# pca20017_power.net
KiCad netlist of a schematic drawn in Altium Designer
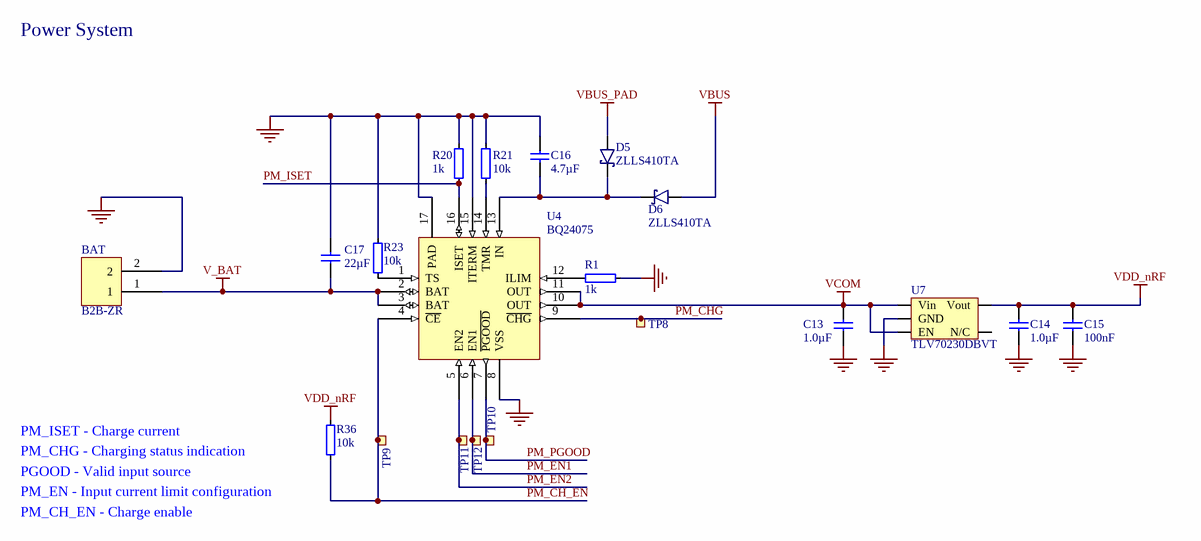
[diagram p0: pca20017_power.SchDoc]

(export (version "E")
  (design (tool "Eeschema 10.0.6"))
  (components
    (comp (ref "BAT")
      (value "B2B-ZR")
      (footprint "B2B-ZR")
      (description "CONN JST 2POS 0.059\" (1.50mm)")
      (fields
        (field (name "MANUFACTURER") "JST Sales America Inc")
        (field (name "MANUFACTURER PART NUMBER") "B2B-ZR(LF)(SN)")
        (field (name "PUBLISHER") "Nordic Semiconductor")
      )
      (libsource (lib "Nordic Passive DB") (part "B2B-ZR"))
    )
    (comp (ref "C13")
      (value "1.0µF")
      (footprint "CAPC1005X04L")
      (description "Capacitor, X5R, ±5%")
      (fields (field (name "PART NUMBER") "C0402-1µ0") (field (name "PUBLISHER") "Nordic Semiconductor"))
      (libsource (lib "Nordic Passive DB") (part "CAP"))
    )
    (comp (ref "C14")
      (value "1.0µF")
      (footprint "CAPC1005X04L")
      (description "Capacitor, X5R, ±5%")
      (fields (field (name "PART NUMBER") "C0402-1µ0") (field (name "PUBLISHER") "Nordic Semiconductor"))
      (libsource (lib "Nordic Passive DB") (part "CAP"))
    )
    (comp (ref "C15")
      (value "100nF")
      (footprint "CAPC1005X04L")
      (description "Capacitor, X7R, ±10%")
      (fields (field (name "PART NUMBER") "C0402-100n") (field (name "PUBLISHER") "Nordic Semiconductor"))
      (libsource (lib "Nordic Passive DB") (part "CAP"))
    )
    (comp (ref "C16")
      (value "4.7µF")
      (footprint "CAPC1005X04L")
      (description "Capacitor, X5R, ±20%")
      (fields (field (name "PART NUMBER") "C0402-4µ7") (field (name "PUBLISHER") "Nordic Semiconductor"))
      (libsource (lib "Nordic Passive DB") (part "CAP"))
    )
    (comp (ref "C17")
      (value "22µF")
      (footprint "CAPC2012X11L")
      (description "Capacitor, X5R, ±10%")
      (fields (field (name "PART NUMBER") "C0805-22µ") (field (name "PUBLISHER") "Nordic Semiconductor"))
      (libsource (lib "Nordic Passive DB") (part "CAP"))
    )
    (comp (ref "D5")
      (value "ZLLS410TA")
      (footprint "SOD-323")
      (description "DIODE SCHOTTKY 10V 0.57A SOD323")
      (fields
        (field (name "MANUFACTURER") "Diodes Incorporated")
        (field (name "2ND SOURCE PART NUMBER") "522-ZLLS410TA")
        (field (name "PUBLISHER") "Nordic Semiconductor")
      )
      (libsource (lib "Nordic Discrete DB") (part "D{colon}SCHOTTKY"))
    )
    (comp (ref "D6")
      (value "ZLLS410TA")
      (footprint "SOD-323")
      (description "DIODE SCHOTTKY 10V 0.57A SOD323")
      (fields
        (field (name "MANUFACTURER") "Diodes Incorporated")
        (field (name "2ND SOURCE PART NUMBER") "522-ZLLS410TA")
        (field (name "PUBLISHER") "Nordic Semiconductor")
      )
      (libsource (lib "Nordic Discrete DB") (part "D{colon}SCHOTTKY"))
    )
    (comp (ref "R1")
      (value "1k")
      (footprint "RESC1005X04L")
      (description "Resistor, ±1%, 0.063W")
      (fields (field (name "PART NUMBER") "R0402-1k0") (field (name "PUBLISHER") "Nordic Semiconductor"))
      (libsource (lib "Nordic Passive DB") (part "RES_1"))
    )
    (comp (ref "R20")
      (value "1k")
      (footprint "RESC1005X04L")
      (description "Resistor, ±1%, 0.063W")
      (fields (field (name "PART NUMBER") "R0402-1k0") (field (name "PUBLISHER") "Nordic Semiconductor"))
      (libsource (lib "Nordic Passive DB") (part "RES_1"))
    )
    (comp (ref "R21")
      (value "10k")
      (footprint "RESC1005X04L")
      (description "Resistor, ±1%, 0.063W")
      (fields (field (name "PART NUMBER") "R0402-10k") (field (name "PUBLISHER") "Nordic Semiconductor"))
      (libsource (lib "Nordic Passive DB") (part "RES_1"))
    )
    (comp (ref "R23")
      (value "10k")
      (footprint "RESC1005X04L")
      (description "Resistor, ±1%, 0.063W")
      (fields (field (name "PART NUMBER") "R0402-10k") (field (name "PUBLISHER") "Nordic Semiconductor"))
      (libsource (lib "Nordic Passive DB") (part "RES_1"))
    )
    (comp (ref "R36")
      (value "10k")
      (footprint "RESC1005X04L")
      (description "Resistor, ±1%, 0.063W")
      (fields (field (name "PART NUMBER") "R0402-10k") (field (name "PUBLISHER") "Nordic Semiconductor"))
      (libsource (lib "Nordic Passive DB") (part "RES_1"))
    )
    (comp (ref "TP8")
      (value "Ø1.0mm,SMD")
      (footprint "TP_SMD_Ø1.0mm")
      (description "1.0mm circular SMD testpad")
      (fields
        (field (name "PART NUMBER") "TP_SMD_Ø1.0MM")
        (field (name "MANUFACTURER") "Nordic Semiconductor")
        (field (name "PUBLISHER") "Nordic Semiconductor")
      )
      (libsource (lib "") (part "TESTPAD_1"))
    )
    (comp (ref "TP9")
      (value "Ø1.0mm,SMD")
      (footprint "TP_SMD_Ø1.0mm")
      (description "1.0mm circular SMD testpad")
      (fields
        (field (name "PART NUMBER") "TP_SMD_Ø1.0MM")
        (field (name "MANUFACTURER") "Nordic Semiconductor")
        (field (name "PUBLISHER") "Nordic Semiconductor")
      )
      (libsource (lib "Nordic Passive DB") (part "TESTPAD"))
    )
    (comp (ref "TP10")
      (value "Ø1.0mm,SMD")
      (footprint "TP_SMD_Ø1.0mm")
      (description "1.0mm circular SMD testpad")
      (fields
        (field (name "PART NUMBER") "TP_SMD_Ø1.0MM")
        (field (name "MANUFACTURER") "Nordic Semiconductor")
        (field (name "PUBLISHER") "Nordic Semiconductor")
      )
      (libsource (lib "Nordic Passive DB") (part "TESTPAD"))
    )
    (comp (ref "TP11")
      (value "Ø1.0mm,SMD")
      (footprint "TP_SMD_Ø1.0mm")
      (description "1.0mm circular SMD testpad")
      (fields
        (field (name "PART NUMBER") "TP_SMD_Ø1.0MM")
        (field (name "MANUFACTURER") "Nordic Semiconductor")
        (field (name "PUBLISHER") "Nordic Semiconductor")
      )
      (libsource (lib "Nordic Passive DB") (part "TESTPAD"))
    )
    (comp (ref "TP12")
      (value "Ø1.0mm,SMD")
      (footprint "TP_SMD_Ø1.0mm")
      (description "1.0mm circular SMD testpad")
      (fields
        (field (name "PART NUMBER") "TP_SMD_Ø1.0MM")
        (field (name "MANUFACTURER") "Nordic Semiconductor")
        (field (name "PUBLISHER") "Nordic Semiconductor")
      )
      (libsource (lib "Nordic Passive DB") (part "TESTPAD"))
    )
    (comp (ref "U4")
      (value "BQ24075")
      (footprint "QFN50P300X300X100_HS-17N")
      (description "IC SINGLE CELL USB LI-ION CHARGER")
      (fields
        (field (name "MANUFACTURER") "Texas Instruments")
        (field (name "MANUFACTURER PART NUMBER") "BQ24075RGTT")
        (field (name "PUBLISHER") "Nordic Semiconductor")
      )
      (libsource (lib "Nordic Active DB") (part "BQ24075"))
    )
    (comp (ref "U7")
      (value "TLV70230DBVT")
      (footprint "SOT-23-5")
      (description "IC REG LDO 3V 300MA SOT23-5")
      (fields
        (field (name "MANUFACTURER") "Texas Instruments")
        (field (name "PUBLISHER") "Nordic Semiconductor")
      )
      (libsource (lib "Nordic Active DB") (part "TLV702xxDBV"))
    )
  )
  (nets
    (net (code "1") (name "/PM_CHG") (class "Default")
      (node (ref "TP8") (pin "1") (pinfunction "1_1") (pintype "passive"))
      (node (ref "U4") (pin "9") (pinfunction "~{CHG}_9") (pintype "output"))
    )
    (net (code "2") (name "/PM_CH_EN") (class "Default")
      (node (ref "R36") (pin "1") (pinfunction "1_1") (pintype "passive"))
      (node (ref "TP9") (pin "1") (pinfunction "1_1") (pintype "passive"))
      (node (ref "U4") (pin "4") (pinfunction "~{CE}_4") (pintype "input"))
    )
    (net (code "3") (name "/PM_EN1") (class "Default")
      (node (ref "TP12") (pin "1") (pinfunction "1_1") (pintype "passive"))
      (node (ref "U4") (pin "6") (pinfunction "EN1_6") (pintype "input"))
    )
    (net (code "4") (name "/PM_EN2") (class "Default")
      (node (ref "TP11") (pin "1") (pinfunction "1_1") (pintype "passive"))
      (node (ref "U4") (pin "5") (pinfunction "EN2_5") (pintype "input"))
    )
    (net (code "5") (name "/PM_ISET") (class "Default")
      (node (ref "R20") (pin "1") (pinfunction "1_1") (pintype "passive"))
      (node (ref "U4") (pin "16") (pinfunction "ISET_16") (pintype "bidirectional"))
    )
    (net (code "6") (name "/PM_PGOOD") (class "Default")
      (node (ref "TP10") (pin "1") (pinfunction "1_1") (pintype "passive"))
      (node (ref "U4") (pin "7") (pinfunction "~{PGOOD}_7") (pintype "output"))
    )
    (net (code "7") (name "GND") (class "Default")
      (node (ref "BAT") (pin "2") (pinfunction "2_2") (pintype "power_in"))
      (node (ref "C13") (pin "1") (pinfunction "1_1") (pintype "passive"))
      (node (ref "C14") (pin "1") (pinfunction "1_1") (pintype "passive"))
      (node (ref "C15") (pin "1") (pinfunction "1_1") (pintype "passive"))
      (node (ref "C16") (pin "2") (pinfunction "2_2") (pintype "passive"))
      (node (ref "C17") (pin "2") (pinfunction "2_2") (pintype "passive"))
      (node (ref "R1") (pin "2") (pinfunction "2_2") (pintype "passive"))
      (node (ref "R20") (pin "2") (pinfunction "2_2") (pintype "passive"))
      (node (ref "R21") (pin "2") (pinfunction "2_2") (pintype "passive"))
      (node (ref "R23") (pin "1") (pinfunction "1_1") (pintype "passive"))
      (node (ref "U4") (pin "15") (pinfunction "ITERM_15") (pintype "input"))
      (node (ref "U4") (pin "17") (pinfunction "PAD_17") (pintype "power_in"))
      (node (ref "U4") (pin "8") (pinfunction "VSS_8") (pintype "power_in"))
      (node (ref "U7") (pin "2") (pinfunction "GND_2") (pintype "passive"))
    )
    (net (code "8") (name "Net-(D5-C)") (class "Default")
      (node (ref "C16") (pin "1") (pinfunction "1_1") (pintype "passive"))
      (node (ref "D5") (pin "3") (pinfunction "C_3") (pintype "passive"))
      (node (ref "D6") (pin "3") (pinfunction "C_3") (pintype "passive"))
      (node (ref "U4") (pin "13") (pinfunction "IN_13") (pintype "input"))
    )
    (net (code "9") (name "Net-(U4-ILIM)") (class "Default")
      (node (ref "R1") (pin "1") (pinfunction "1_1") (pintype "passive"))
      (node (ref "U4") (pin "12") (pinfunction "ILIM_12") (pintype "input"))
    )
    (net (code "10") (name "Net-(U4-TMR)") (class "Default")
      (node (ref "R21") (pin "1") (pinfunction "1_1") (pintype "passive"))
      (node (ref "U4") (pin "14") (pinfunction "TMR_14") (pintype "input"))
    )
    (net (code "11") (name "Net-(U4-TS)") (class "Default")
      (node (ref "R23") (pin "2") (pinfunction "2_2") (pintype "passive"))
      (node (ref "U4") (pin "1") (pinfunction "TS_1") (pintype "input"))
    )
    (net (code "12") (name "VBUS") (class "Default")
      (node (ref "D6") (pin "1") (pinfunction "A_1") (pintype "passive"))
    )
    (net (code "13") (name "VBUS_PAD") (class "Default")
      (node (ref "D5") (pin "1") (pinfunction "A_1") (pintype "passive"))
    )
    (net (code "14") (name "VCOM") (class "Default")
      (node (ref "C13") (pin "2") (pinfunction "2_2") (pintype "passive"))
      (node (ref "U4") (pin "10") (pinfunction "OUT_10") (pintype "output"))
      (node (ref "U4") (pin "11") (pinfunction "OUT_11") (pintype "output"))
      (node (ref "U7") (pin "1") (pinfunction "Vin_1") (pintype "passive"))
      (node (ref "U7") (pin "3") (pinfunction "EN_3") (pintype "passive"))
    )
    (net (code "15") (name "VDD_nRF") (class "Default")
      (node (ref "C14") (pin "2") (pinfunction "2_2") (pintype "passive"))
      (node (ref "C15") (pin "2") (pinfunction "2_2") (pintype "passive"))
      (node (ref "R36") (pin "2") (pinfunction "2_2") (pintype "passive"))
      (node (ref "U7") (pin "5") (pinfunction "Vout_5") (pintype "passive"))
    )
    (net (code "16") (name "V_BAT") (class "Default")
      (node (ref "BAT") (pin "1") (pinfunction "1_1") (pintype "power_in"))
      (node (ref "C17") (pin "1") (pinfunction "1_1") (pintype "passive"))
      (node (ref "U4") (pin "2") (pinfunction "BAT_2") (pintype "bidirectional"))
      (node (ref "U4") (pin "3") (pinfunction "BAT_3") (pintype "bidirectional"))
    )
    (net (code "17") (name "unconnected-(U7-N{slash}C-Pad4)") (class "Default")
      (node (ref "U7") (pin "4") (pinfunction "N/C_4") (pintype "passive"))
    )
  )
)
